# DS18B20.net
KiCad netlist of a schematic drawn in Altium Designer
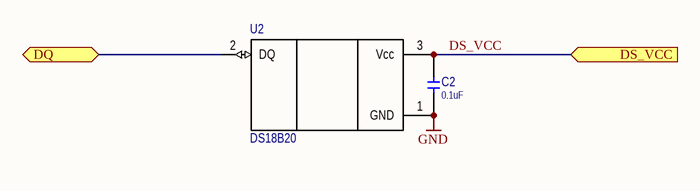
[diagram p0: DS18B20.SchDoc]

(export (version "E")
  (design (tool "Eeschema 10.0.6"))
  (components
    (comp (ref "C2")
      (value "0.1uF")
      (footprint "CERCAP 0402")
      (description "Capacitor")
      (fields (field (name "Comment") "CERCAP 0402 0.1uF * X7R"))
      (libsource (lib "!main") (part "!Capacitor"))
    )
    (comp (ref "U2")
      (value "DS18B20")
      (footprint "TO-92")
      (description "Temp")
      (libsource (lib "sensors") (part "DS18B20"))
    )
  )
  (nets
    (net (code "1") (name "/DQ") (class "Default")
      (node (ref "U2") (pin "2") (pinfunction "DQ_2") (pintype "bidirectional"))
    )
    (net (code "2") (name "/DS_VCC") (class "Default")
      (node (ref "C2") (pin "2") (pintype "passive"))
      (node (ref "U2") (pin "3") (pinfunction "Vcc_3") (pintype "power_in"))
    )
    (net (code "3") (name "GND") (class "Default")
      (node (ref "C2") (pin "1") (pintype "passive"))
      (node (ref "U2") (pin "1") (pinfunction "GND_1") (pintype "power_in"))
    )
  )
)
